# LatarDetect.net
KiCad netlist of a schematic drawn in EAGLE
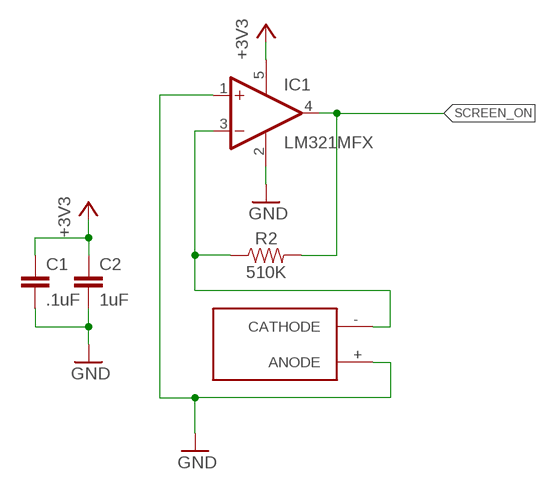
[diagram p0: schematic, sheet 1]

(export (version "E")
  (design (tool "Eeschema 10.0.6"))
  (components
    (comp (ref "C1")
      (value ".1uF")
      (footprint "eagle-import:C0805")
      (libsource (lib "eagle-import") (part "C-EUC0805"))
    )
    (comp (ref "C2")
      (value "1uF")
      (footprint "eagle-import:C0805")
      (libsource (lib "eagle-import") (part "C-EUC0805"))
    )
    (comp (ref "IC1")
      (value "LM321MFX")
      (footprint "eagle-import:SOT23-5")
      (libsource (lib "eagle-import") (part "LM321?MFX"))
    )
    (comp (ref "R2")
      (value "510K")
      (footprint "eagle-import:0805")
      (libsource (lib "eagle-import") (part "RESISTOR0805"))
    )
    (comp (ref "U$1")
      (value "BPW34S-Z")
      (footprint "eagle-import:BPW34S-Z")
      (libsource (lib "eagle-import") (part "BPW34S-Z"))
    )
  )
  (nets
    (net (code "1") (name "+3V3") (class "Default")
      (node (ref "C1") (pin "1") (pinfunction "1_1") (pintype "passive"))
      (node (ref "C2") (pin "1") (pinfunction "1_1") (pintype "passive"))
      (node (ref "IC1") (pin "5") (pinfunction "V+_5") (pintype "power_in"))
    )
    (net (code "2") (name "GND") (class "Default")
      (node (ref "C1") (pin "2") (pinfunction "2_2") (pintype "passive"))
      (node (ref "C2") (pin "2") (pinfunction "2_2") (pintype "passive"))
      (node (ref "IC1") (pin "1") (pinfunction "+IN_1") (pintype "input"))
      (node (ref "IC1") (pin "2") (pinfunction "V-_2") (pintype "power_in"))
      (node (ref "U$1") (pin "+") (pinfunction "ANODE_+") (pintype "bidirectional"))
    )
    (net (code "3") (name "Net-(IC1--IN)") (class "Default")
      (node (ref "IC1") (pin "3") (pinfunction "-IN_3") (pintype "input"))
      (node (ref "R2") (pin "1") (pinfunction "1_1") (pintype "passive"))
      (node (ref "U$1") (pin "-") (pinfunction "CATHODE_-") (pintype "bidirectional"))
    )
    (net (code "4") (name "SCREEN_ON") (class "Default")
      (node (ref "IC1") (pin "4") (pinfunction "OUT_4") (pintype "output"))
      (node (ref "R2") (pin "2") (pinfunction "2_2") (pintype "passive"))
    )
  )
)
